# NoteTaker.net
KiCad netlist of a schematic drawn in EAGLE
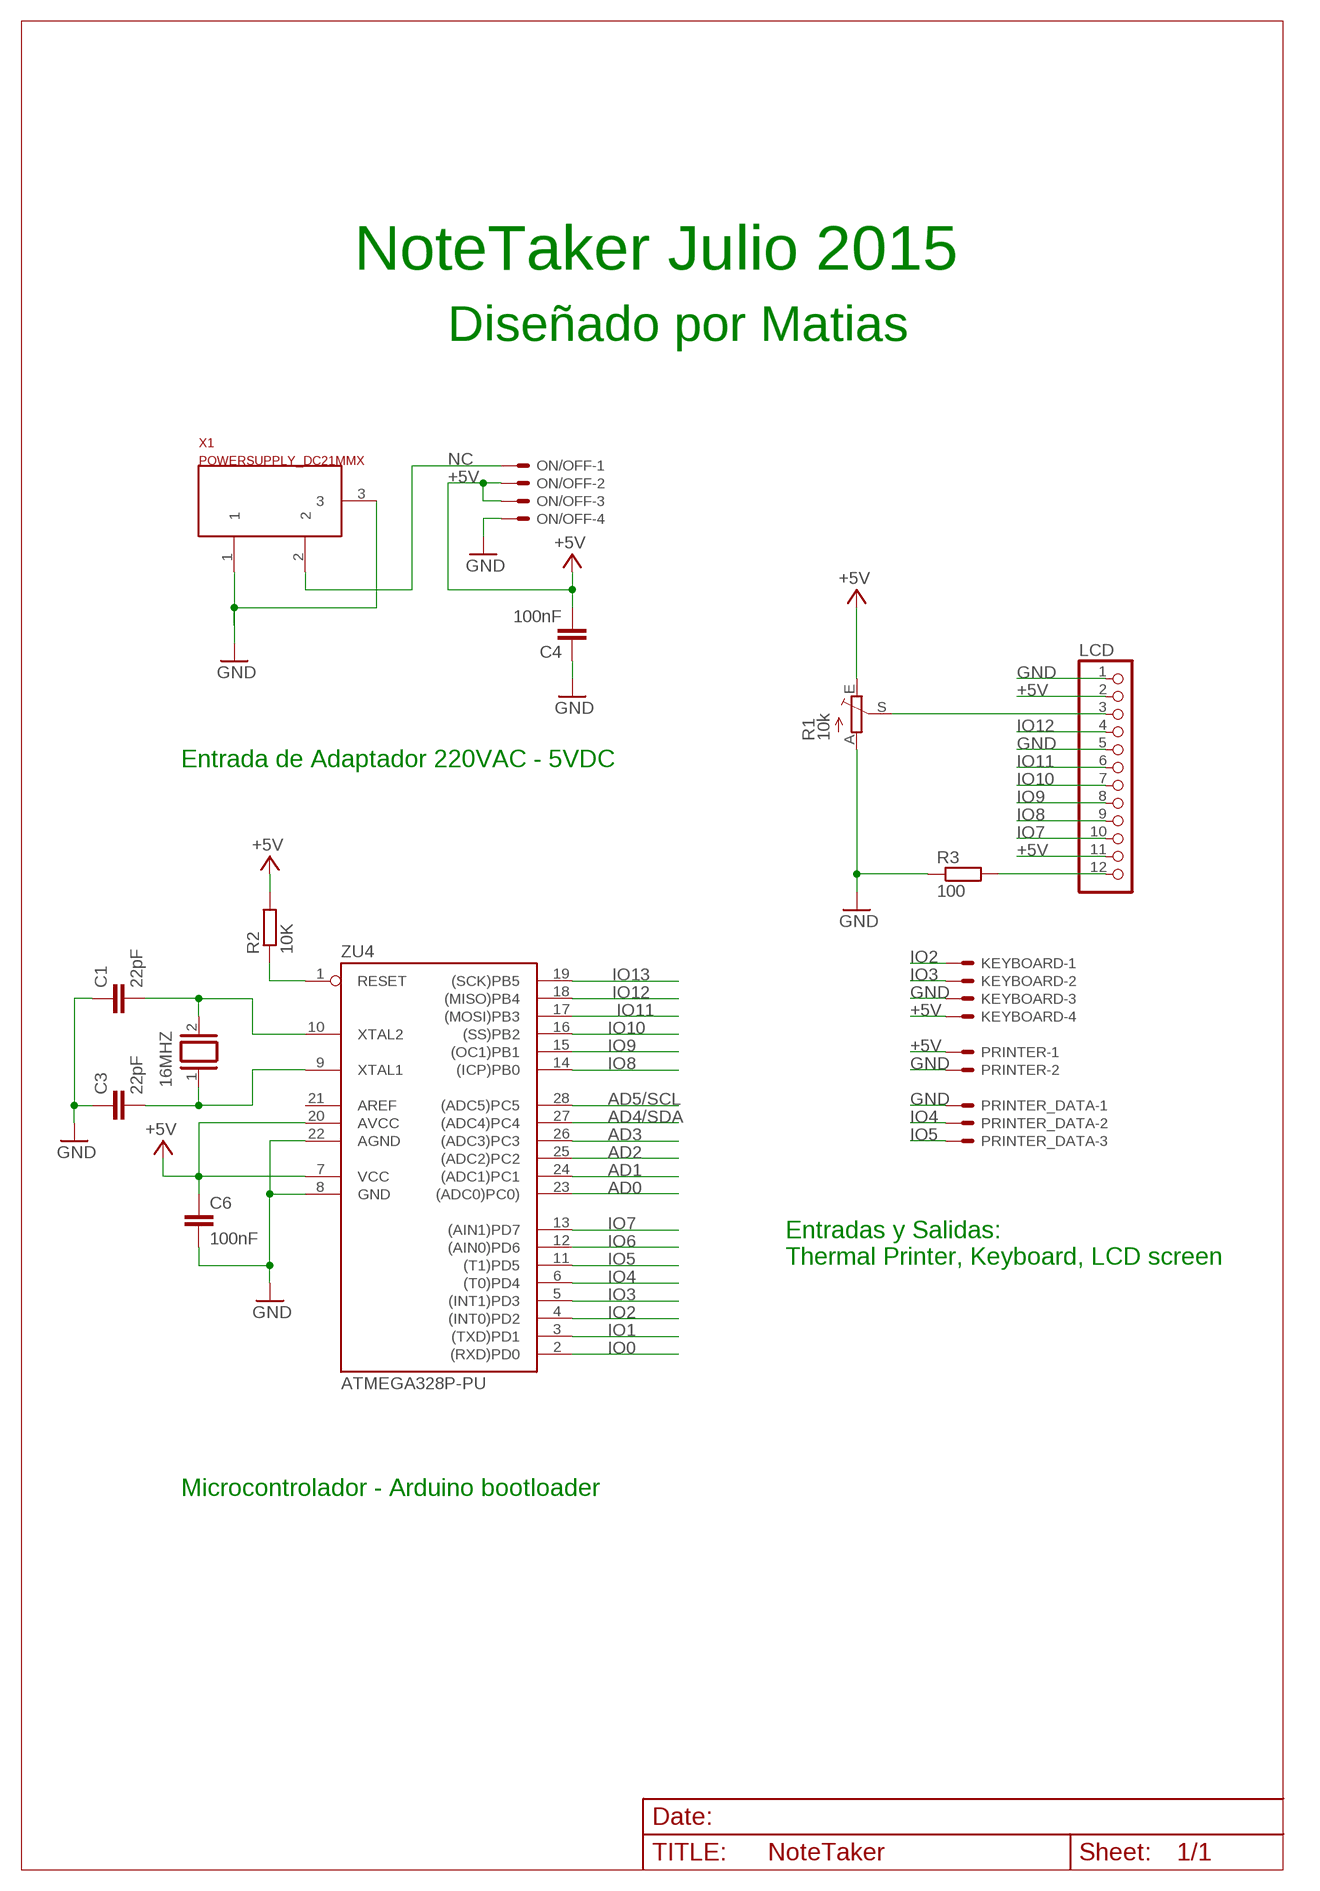
[diagram p0: schematic, sheet 1]

(export (version "E")
  (design (tool "Eeschema 10.0.6"))
  (components
    (comp (ref "16MHZ")
      (value "XTAL/S")
      (footprint "eagle-import:QS")
      (libsource (lib "eagle-import") (part "XTAL/S"))
    )
    (comp (ref "C1")
      (value "22pF")
      (footprint "eagle-import:C025-025X050")
      (libsource (lib "eagle-import") (part "C-EU025-025X050"))
    )
    (comp (ref "C3")
      (value "22pF")
      (footprint "eagle-import:C025-025X050")
      (libsource (lib "eagle-import") (part "C-EU025-025X050"))
    )
    (comp (ref "C4")
      (value "100nF")
      (footprint "eagle-import:C025-025X050")
      (libsource (lib "eagle-import") (part "C-EU025-025X050"))
    )
    (comp (ref "C6")
      (value "100nF")
      (footprint "eagle-import:C025-025X050")
      (libsource (lib "eagle-import") (part "C-EU025-025X050"))
    )
    (comp (ref "KEYBOARD")
      (value "KK-156-4")
      (footprint "eagle-import:KK-156-4")
      (libsource (lib "eagle-import") (part "KK-156-4"))
    )
    (comp (ref "LCD")
      (value "PINHD-1X12")
      (footprint "eagle-import:1X12")
      (libsource (lib "eagle-import") (part "PINHD-1X12"))
    )
    (comp (ref "ON/OFF")
      (value "KK-156-4")
      (footprint "eagle-import:KK-156-4")
      (libsource (lib "eagle-import") (part "KK-156-4"))
    )
    (comp (ref "PRINTER")
      (value "KK-156-2")
      (footprint "eagle-import:KK-156-2")
      (libsource (lib "eagle-import") (part "KK-156-2"))
    )
    (comp (ref "PRINTER_DATA")
      (value "KK-156-3")
      (footprint "eagle-import:KK-156-3")
      (libsource (lib "eagle-import") (part "KK-156-3"))
    )
    (comp (ref "R1")
      (value "10k")
      (footprint "eagle-import:S64W")
      (libsource (lib "eagle-import") (part "TRIM_EU-S64W"))
    )
    (comp (ref "R2")
      (value "10K")
      (footprint "eagle-import:0207_10")
      (libsource (lib "eagle-import") (part "R-EU_0207/10"))
    )
    (comp (ref "R3")
      (value "100")
      (footprint "eagle-import:0207_10")
      (libsource (lib "eagle-import") (part "R-EU_0207/10"))
    )
    (comp (ref "X1")
      (value "POWERSUPPLY_DC21MMX")
      (footprint "eagle-import:POWERSUPPLY_DC-21MM")
      (libsource (lib "eagle-import") (part "POWERSUPPLY_DC21MMX"))
    )
    (comp (ref "ZU4")
      (value "ATMEGA328P-PU")
      (footprint "eagle-import:DIL28-3")
      (libsource (lib "eagle-import") (part "ATMEGA328P-PU"))
    )
  )
  (nets
    (net (code "1") (name "+5V") (class "Default")
      (node (ref "C4") (pin "2") (pinfunction "2_2") (pintype "passive"))
      (node (ref "C6") (pin "1") (pinfunction "1_1") (pintype "passive"))
      (node (ref "KEYBOARD") (pin "4") (pinfunction "S_4") (pintype "passive"))
      (node (ref "LCD") (pin "11") (pinfunction "11_11") (pintype "passive"))
      (node (ref "LCD") (pin "2") (pinfunction "2_2") (pintype "passive"))
      (node (ref "ON/OFF") (pin "2") (pinfunction "S_2") (pintype "passive"))
      (node (ref "ON/OFF") (pin "3") (pinfunction "S_3") (pintype "passive"))
      (node (ref "PRINTER") (pin "1") (pinfunction "S_1") (pintype "passive"))
      (node (ref "R1") (pin "E") (pinfunction "E_E") (pintype "passive"))
      (node (ref "R2") (pin "2") (pinfunction "2_2") (pintype "passive"))
      (node (ref "ZU4") (pin "20") (pinfunction "AVCC_20") (pintype "power_in"))
      (node (ref "ZU4") (pin "7") (pinfunction "VCC_7") (pintype "power_in"))
    )
    (net (code "2") (name "/AD0") (class "Default")
      (node (ref "ZU4") (pin "23") (pinfunction "(ADC0)PC0)_23") (pintype "bidirectional"))
    )
    (net (code "3") (name "/AD1") (class "Default")
      (node (ref "ZU4") (pin "24") (pinfunction "(ADC1)PC1_24") (pintype "bidirectional"))
    )
    (net (code "4") (name "/AD2") (class "Default")
      (node (ref "ZU4") (pin "25") (pinfunction "(ADC2)PC2_25") (pintype "bidirectional"))
    )
    (net (code "5") (name "/AD3") (class "Default")
      (node (ref "ZU4") (pin "26") (pinfunction "(ADC3)PC3_26") (pintype "bidirectional"))
    )
    (net (code "6") (name "/AD4{slash}SDA") (class "Default")
      (node (ref "ZU4") (pin "27") (pinfunction "(ADC4)PC4_27") (pintype "bidirectional"))
    )
    (net (code "7") (name "/AD5{slash}SCL") (class "Default")
      (node (ref "ZU4") (pin "28") (pinfunction "(ADC5)PC5_28") (pintype "bidirectional"))
    )
    (net (code "8") (name "/IO0") (class "Default")
      (node (ref "ZU4") (pin "2") (pinfunction "(RXD)PD0_2") (pintype "bidirectional"))
    )
    (net (code "9") (name "/IO1") (class "Default")
      (node (ref "ZU4") (pin "3") (pinfunction "(TXD)PD1_3") (pintype "bidirectional"))
    )
    (net (code "10") (name "/IO2") (class "Default")
      (node (ref "KEYBOARD") (pin "1") (pinfunction "S_1") (pintype "passive"))
      (node (ref "ZU4") (pin "4") (pinfunction "(INT0)PD2_4") (pintype "bidirectional"))
    )
    (net (code "11") (name "/IO3") (class "Default")
      (node (ref "KEYBOARD") (pin "2") (pinfunction "S_2") (pintype "passive"))
      (node (ref "ZU4") (pin "5") (pinfunction "(INT1)PD3_5") (pintype "bidirectional"))
    )
    (net (code "12") (name "/IO4") (class "Default")
      (node (ref "PRINTER_DATA") (pin "2") (pinfunction "S_2") (pintype "passive"))
      (node (ref "ZU4") (pin "6") (pinfunction "(T0)PD4_6") (pintype "bidirectional"))
    )
    (net (code "13") (name "/IO5") (class "Default")
      (node (ref "PRINTER_DATA") (pin "3") (pinfunction "S_3") (pintype "passive"))
      (node (ref "ZU4") (pin "11") (pinfunction "(T1)PD5_11") (pintype "bidirectional"))
    )
    (net (code "14") (name "/IO6") (class "Default")
      (node (ref "ZU4") (pin "12") (pinfunction "(AIN0)PD6_12") (pintype "bidirectional"))
    )
    (net (code "15") (name "/IO7") (class "Default")
      (node (ref "LCD") (pin "10") (pinfunction "10_10") (pintype "passive"))
      (node (ref "ZU4") (pin "13") (pinfunction "(AIN1)PD7_13") (pintype "bidirectional"))
    )
    (net (code "16") (name "/IO8") (class "Default")
      (node (ref "LCD") (pin "9") (pinfunction "9_9") (pintype "passive"))
      (node (ref "ZU4") (pin "14") (pinfunction "(ICP)PB0_14") (pintype "bidirectional"))
    )
    (net (code "17") (name "/IO9") (class "Default")
      (node (ref "LCD") (pin "8") (pinfunction "8_8") (pintype "passive"))
      (node (ref "ZU4") (pin "15") (pinfunction "(OC1)PB1_15") (pintype "bidirectional"))
    )
    (net (code "18") (name "/IO10") (class "Default")
      (node (ref "LCD") (pin "7") (pinfunction "7_7") (pintype "passive"))
      (node (ref "ZU4") (pin "16") (pinfunction "(SS)PB2_16") (pintype "bidirectional"))
    )
    (net (code "19") (name "/IO11") (class "Default")
      (node (ref "LCD") (pin "6") (pinfunction "6_6") (pintype "passive"))
      (node (ref "ZU4") (pin "17") (pinfunction "(MOSI)PB3_17") (pintype "bidirectional"))
    )
    (net (code "20") (name "/IO12") (class "Default")
      (node (ref "LCD") (pin "4") (pinfunction "4_4") (pintype "passive"))
      (node (ref "ZU4") (pin "18") (pinfunction "(MISO)PB4_18") (pintype "bidirectional"))
    )
    (net (code "21") (name "/IO13") (class "Default")
      (node (ref "ZU4") (pin "19") (pinfunction "(SCK)PB5_19") (pintype "bidirectional"))
    )
    (net (code "22") (name "/NC") (class "Default")
      (node (ref "ON/OFF") (pin "1") (pinfunction "S_1") (pintype "passive"))
      (node (ref "X1") (pin "2") (pinfunction "2_2") (pintype "power_in"))
    )
    (net (code "23") (name "GND") (class "Default")
      (node (ref "C1") (pin "1") (pinfunction "1_1") (pintype "passive"))
      (node (ref "C3") (pin "1") (pinfunction "1_1") (pintype "passive"))
      (node (ref "C4") (pin "1") (pinfunction "1_1") (pintype "passive"))
      (node (ref "C6") (pin "2") (pinfunction "2_2") (pintype "passive"))
      (node (ref "KEYBOARD") (pin "3") (pinfunction "S_3") (pintype "passive"))
      (node (ref "LCD") (pin "1") (pinfunction "1_1") (pintype "passive"))
      (node (ref "LCD") (pin "5") (pinfunction "5_5") (pintype "passive"))
      (node (ref "ON/OFF") (pin "4") (pinfunction "S_4") (pintype "passive"))
      (node (ref "PRINTER") (pin "2") (pinfunction "S_2") (pintype "passive"))
      (node (ref "PRINTER_DATA") (pin "1") (pinfunction "S_1") (pintype "passive"))
      (node (ref "R1") (pin "A") (pinfunction "A_A") (pintype "passive"))
      (node (ref "R3") (pin "1") (pinfunction "1_1") (pintype "passive"))
      (node (ref "X1") (pin "1") (pinfunction "1_1") (pintype "power_in"))
      (node (ref "X1") (pin "3") (pinfunction "3_3") (pintype "power_in"))
      (node (ref "ZU4") (pin "22") (pinfunction "AGND_22") (pintype "power_in"))
      (node (ref "ZU4") (pin "8") (pinfunction "GND_8") (pintype "power_in"))
    )
    (net (code "24") (name "Net-(LCD-Pad3)") (class "Default")
      (node (ref "LCD") (pin "3") (pinfunction "3_3") (pintype "passive"))
      (node (ref "R1") (pin "S") (pinfunction "S_S") (pintype "passive"))
    )
    (net (code "25") (name "Net-(LCD-Pad12)") (class "Default")
      (node (ref "LCD") (pin "12") (pinfunction "12_12") (pintype "passive"))
      (node (ref "R3") (pin "2") (pinfunction "2_2") (pintype "passive"))
    )
    (net (code "26") (name "Net-(ZU4-RESET)") (class "Default")
      (node (ref "R2") (pin "1") (pinfunction "1_1") (pintype "passive"))
      (node (ref "ZU4") (pin "1") (pinfunction "RESET_1") (pintype "input"))
    )
    (net (code "27") (name "Net-(ZU4-XTAL1)") (class "Default")
      (node (ref "16MHZ") (pin "1") (pinfunction "1_1") (pintype "passive"))
      (node (ref "C3") (pin "2") (pinfunction "2_2") (pintype "passive"))
      (node (ref "ZU4") (pin "9") (pinfunction "XTAL1_9") (pintype "bidirectional"))
    )
    (net (code "28") (name "Net-(ZU4-XTAL2)") (class "Default")
      (node (ref "16MHZ") (pin "2") (pinfunction "2_2") (pintype "passive"))
      (node (ref "C1") (pin "2") (pinfunction "2_2") (pintype "passive"))
      (node (ref "ZU4") (pin "10") (pinfunction "XTAL2_10") (pintype "bidirectional"))
    )
    (net (code "29") (name "unconnected-(ZU4-AREF-Pad21)") (class "Default")
      (node (ref "ZU4") (pin "21") (pinfunction "AREF_21") (pintype "passive"))
    )
  )
)
